# LEDs.net
KiCad netlist of a schematic drawn in Altium Designer
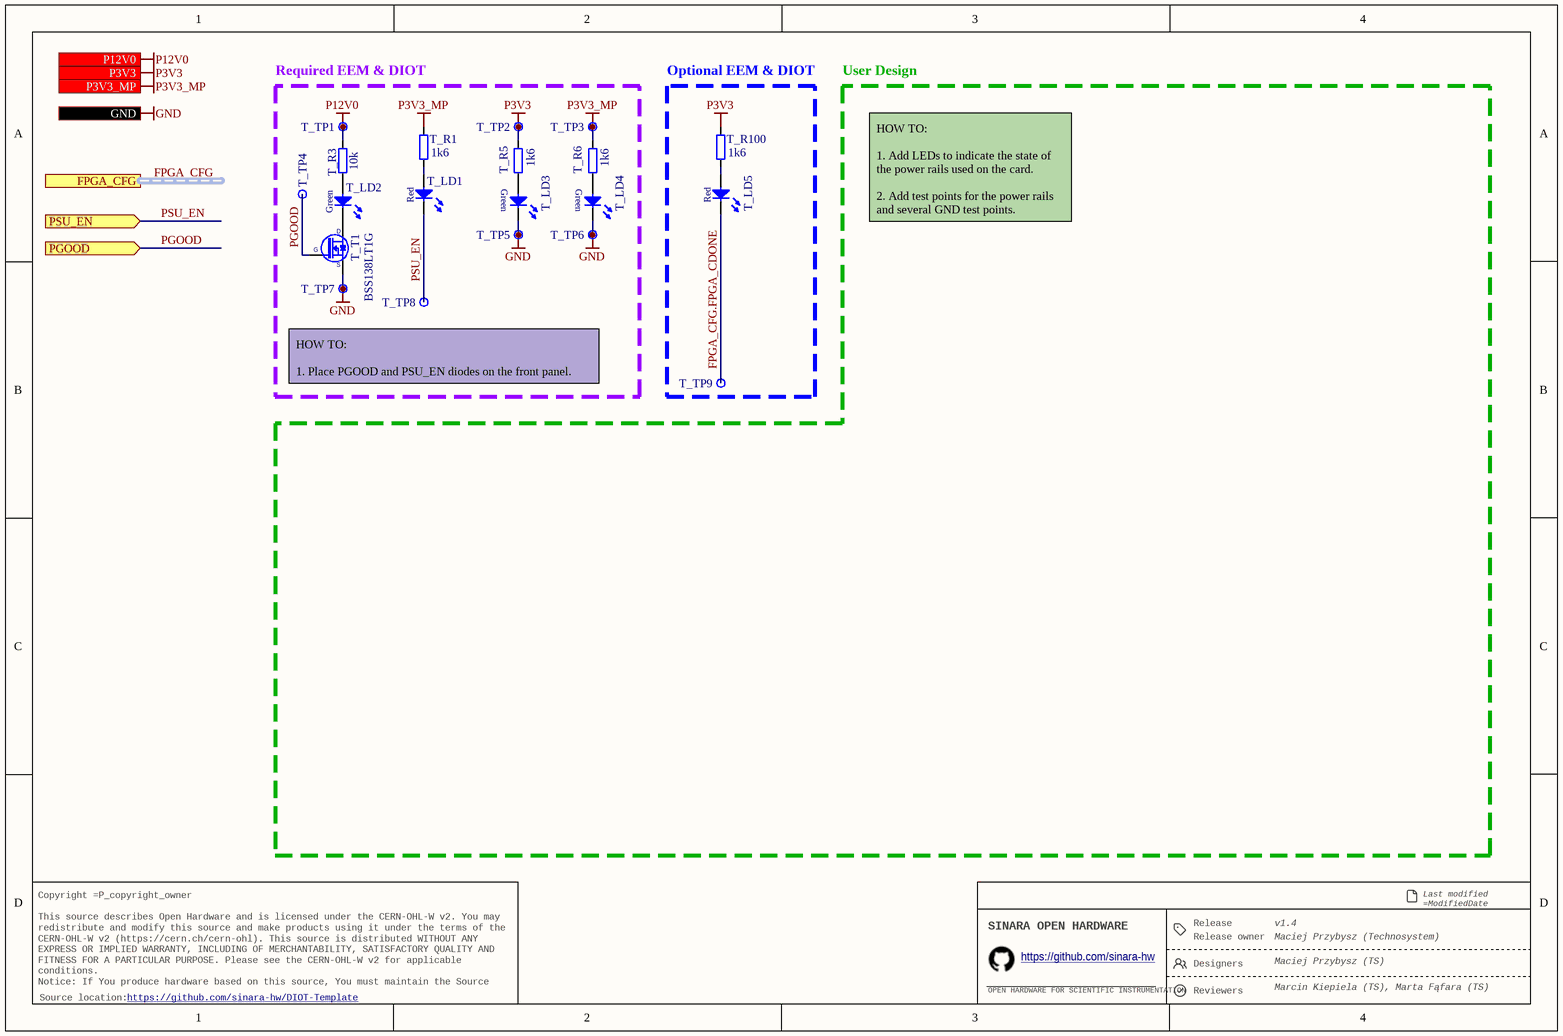
[diagram p0: LEDs.SchDoc]

(export (version "E")
  (design (tool "Eeschema 10.0.6"))
  (components
    (comp (ref "T_LD1")
      (value "Red")
      (footprint "LED_AVAGO_HSMC-C110")
      (description "LED Red 1C 2A")
      (fields
        (field (name "PART NUMBER") "LED_AVAGO_HSMC-C110")
        (field (name "MANUFACTURER") "AVAGO TECHNOLOGIES")
        (field (name "AUTHOR") "CERN DEM JMW")
      )
      (libsource (lib "ICs And Semiconductors") (part "LED Red 1C 2A"))
    )
    (comp (ref "T_LD2")
      (value "Green")
      (footprint "LED_AVAGO_HSME-C110")
      (description "LED Green 1C 2A")
      (fields
        (field (name "PART NUMBER") "LED_AVAGO_HSME-C110")
        (field (name "MANUFACTURER") "AVAGO TECHNOLOGIES")
        (field (name "AUTHOR") "CERN DEM JMW")
      )
      (libsource (lib "") (part "LED Green 1C 2A_1"))
    )
    (comp (ref "T_LD3")
      (value "Green")
      (footprint "LED_KINGBRIGHT_KPH-1608CGCK")
      (description "LED Green 1C 2A")
      (fields
        (field (name "PART NUMBER") "LED_KINGBRIGHT_KPH-1608CGCK")
        (field (name "MANUFACTURER") "KINGBRIGHT")
        (field (name "AUTHOR") "CERN DEM JLC")
      )
      (libsource (lib "ICs And Semiconductors") (part "LED Green 1C 2A"))
    )
    (comp (ref "T_LD4")
      (value "Green")
      (footprint "LED_KINGBRIGHT_KPH-1608CGCK")
      (description "LED Green 1C 2A")
      (fields
        (field (name "PART NUMBER") "LED_KINGBRIGHT_KPH-1608CGCK")
        (field (name "MANUFACTURER") "KINGBRIGHT")
        (field (name "AUTHOR") "CERN DEM JLC")
      )
      (libsource (lib "ICs And Semiconductors") (part "LED Green 1C 2A"))
    )
    (comp (ref "T_LD5")
      (value "Red")
      (footprint "LED_AVAGO_HSMC-C110")
      (description "LED Red 1C 2A")
      (fields
        (field (name "PART NUMBER") "LED_AVAGO_HSMC-C110")
        (field (name "MANUFACTURER") "AVAGO TECHNOLOGIES")
        (field (name "AUTHOR") "CERN DEM JMW")
      )
      (libsource (lib "ICs And Semiconductors") (part "LED Red 1C 2A"))
    )
    (comp (ref "T_R1")
      (value "1k6")
      (footprint "RESC1005X40N")
      (description "Resistor - 1%")
      (fields
        (field (name "PART NUMBER") "R0402_1K6_1%_0.0625W_100PPM")
        (field (name "POWER") "0.0625W")
        (field (name "AUTHOR") "CERN DEM JLC")
      )
      (libsource (lib "Resistors") (part "Resistor - 1%"))
    )
    (comp (ref "T_R3")
      (value "10k")
      (footprint "RESC1005X40N")
      (description "Resistor - 1%")
      (fields
        (field (name "PART NUMBER") "R0402_10K_1%_0.0625W_100PPM")
        (field (name "POWER") "0.0625W")
        (field (name "AUTHOR") "CERN DEM JLC")
      )
      (libsource (lib "Resistors") (part "Resistor - 1%"))
    )
    (comp (ref "T_R5")
      (value "1k6")
      (footprint "RESC1005X40N")
      (description "Resistor - 1%")
      (fields
        (field (name "PART NUMBER") "R0402_1K6_1%_0.0625W_100PPM")
        (field (name "POWER") "0.0625W")
        (field (name "AUTHOR") "CERN DEM JLC")
      )
      (libsource (lib "Resistors") (part "Resistor - 1%"))
    )
    (comp (ref "T_R6")
      (value "1k6")
      (footprint "RESC1005X40N")
      (description "Resistor - 1%")
      (fields
        (field (name "PART NUMBER") "R0402_1K6_1%_0.0625W_100PPM")
        (field (name "POWER") "0.0625W")
        (field (name "AUTHOR") "CERN DEM JLC")
      )
      (libsource (lib "Resistors") (part "Resistor - 1%"))
    )
    (comp (ref "T_R100")
      (value "1k6")
      (footprint "RESC1005X40N")
      (description "Resistor - 1%")
      (fields
        (field (name "PART NUMBER") "R0402_1K6_1%_0.0625W_100PPM")
        (field (name "POWER") "0.0625W")
        (field (name "AUTHOR") "CERN DEM JLC")
      )
      (libsource (lib "Resistors") (part "Resistor - 1%"))
    )
    (comp (ref "T_T1")
      (value "BSS138LT1G")
      (footprint "SOT95P240X110-3N")
      (description "N-CHANNEL MOSFET WITH DIODE")
      (fields
        (field (name "MANUFACTURER") "ON SEMICONDUCTOR")
        (field (name "MANUFACTURER PART NUMBER") "BSS138L")
        (field (name "AUTHOR") "CERN DEM JLC")
      )
      (libsource (lib "ICs And Semiconductors") (part "N-MOSFET-D 1G 2S 3D"))
    )
    (comp (ref "T_TP1")
      (value "Test Point")
      (footprint "TPS127")
      (fields (field (name "PART NUMBER") "SMD_PAD_1.27X1.27MM") (field (name "AUTHOR") "CERN DEM JLC"))
      (libsource (lib "Eletro-mechanical") (part "Test Point"))
    )
    (comp (ref "T_TP2")
      (value "Test Point")
      (footprint "TPS127")
      (fields (field (name "PART NUMBER") "SMD_PAD_1.27X1.27MM") (field (name "AUTHOR") "CERN DEM JLC"))
      (libsource (lib "Eletro-mechanical") (part "Test Point"))
    )
    (comp (ref "T_TP3")
      (value "Test Point")
      (footprint "TPS127")
      (fields (field (name "PART NUMBER") "SMD_PAD_1.27X1.27MM") (field (name "AUTHOR") "CERN DEM JLC"))
      (libsource (lib "Eletro-mechanical") (part "Test Point"))
    )
    (comp (ref "T_TP4")
      (value "Test Point")
      (footprint "TPS127")
      (fields (field (name "PART NUMBER") "SMD_PAD_1.27X1.27MM") (field (name "AUTHOR") "CERN DEM JLC"))
      (libsource (lib "Eletro-mechanical") (part "Test Point"))
    )
    (comp (ref "T_TP5")
      (value "Test Point")
      (footprint "TPS127")
      (fields (field (name "PART NUMBER") "SMD_PAD_1.27X1.27MM") (field (name "AUTHOR") "CERN DEM JLC"))
      (libsource (lib "Eletro-mechanical") (part "Test Point"))
    )
    (comp (ref "T_TP6")
      (value "Test Point")
      (footprint "TPS127")
      (fields (field (name "PART NUMBER") "SMD_PAD_1.27X1.27MM") (field (name "AUTHOR") "CERN DEM JLC"))
      (libsource (lib "Eletro-mechanical") (part "Test Point"))
    )
    (comp (ref "T_TP7")
      (value "Test Point")
      (footprint "TPS127")
      (fields (field (name "PART NUMBER") "SMD_PAD_1.27X1.27MM") (field (name "AUTHOR") "CERN DEM JLC"))
      (libsource (lib "Eletro-mechanical") (part "Test Point"))
    )
    (comp (ref "T_TP8")
      (value "Test Point")
      (footprint "TPS127")
      (fields (field (name "PART NUMBER") "SMD_PAD_1.27X1.27MM") (field (name "AUTHOR") "CERN DEM JLC"))
      (libsource (lib "Eletro-mechanical") (part "Test Point"))
    )
    (comp (ref "T_TP9")
      (value "Test Point")
      (footprint "TPS127")
      (fields (field (name "PART NUMBER") "SMD_PAD_1.27X1.27MM") (field (name "AUTHOR") "CERN DEM JLC"))
      (libsource (lib "Eletro-mechanical") (part "Test Point"))
    )
  )
  (nets
    (net (code "2") (name "/FPGA_CFG.FPGA_CDONE") (class "Default")
      (node (ref "T_LD5") (pin "1") (pinfunction "C_1") (pintype "passive"))
      (node (ref "T_TP9") (pin "1") (pinfunction "1_1") (pintype "bidirectional"))
    )
    (net (code "3") (name "/PGOOD") (class "Default")
      (node (ref "T_T1") (pin "1") (pinfunction "G_1") (pintype "passive"))
      (node (ref "T_TP4") (pin "1") (pinfunction "1_1") (pintype "bidirectional"))
    )
    (net (code "4") (name "/PSU_EN") (class "Default")
      (node (ref "T_LD1") (pin "1") (pinfunction "C_1") (pintype "passive"))
      (node (ref "T_TP8") (pin "1") (pinfunction "1_1") (pintype "bidirectional"))
    )
    (net (code "6") (name "GND") (class "Default")
      (node (ref "T_LD3") (pin "1") (pinfunction "C_1") (pintype "passive"))
      (node (ref "T_LD4") (pin "1") (pinfunction "C_1") (pintype "passive"))
      (node (ref "T_T1") (pin "2") (pinfunction "S_2") (pintype "passive"))
      (node (ref "T_TP5") (pin "1") (pinfunction "1_1") (pintype "bidirectional"))
      (node (ref "T_TP6") (pin "1") (pinfunction "1_1") (pintype "bidirectional"))
      (node (ref "T_TP7") (pin "1") (pinfunction "1_1") (pintype "bidirectional"))
    )
    (net (code "7") (name "Net-(T_LD1-A)") (class "Default")
      (node (ref "T_LD1") (pin "2") (pinfunction "A_2") (pintype "passive"))
      (node (ref "T_R1") (pin "1") (pinfunction "1_1") (pintype "passive"))
    )
    (net (code "8") (name "Net-(T_LD2-A)") (class "Default")
      (node (ref "T_LD2") (pin "2") (pinfunction "A_2") (pintype "passive"))
      (node (ref "T_R3") (pin "2") (pinfunction "2_2") (pintype "passive"))
    )
    (net (code "9") (name "Net-(T_LD2-C)") (class "Default")
      (node (ref "T_LD2") (pin "1") (pinfunction "C_1") (pintype "passive"))
      (node (ref "T_T1") (pin "3") (pinfunction "D_3") (pintype "passive"))
    )
    (net (code "10") (name "Net-(T_LD3-A)") (class "Default")
      (node (ref "T_LD3") (pin "2") (pinfunction "A_2") (pintype "passive"))
      (node (ref "T_R5") (pin "1") (pinfunction "1_1") (pintype "passive"))
    )
    (net (code "11") (name "Net-(T_LD4-A)") (class "Default")
      (node (ref "T_LD4") (pin "2") (pinfunction "A_2") (pintype "passive"))
      (node (ref "T_R6") (pin "1") (pinfunction "1_1") (pintype "passive"))
    )
    (net (code "12") (name "Net-(T_LD5-A)") (class "Default")
      (node (ref "T_LD5") (pin "2") (pinfunction "A_2") (pintype "passive"))
      (node (ref "T_R100") (pin "1") (pinfunction "1_1") (pintype "passive"))
    )
    (net (code "13") (name "P3V3") (class "Default")
      (node (ref "T_R100") (pin "2") (pinfunction "2_2") (pintype "passive"))
      (node (ref "T_R5") (pin "2") (pinfunction "2_2") (pintype "passive"))
      (node (ref "T_TP2") (pin "1") (pinfunction "1_1") (pintype "bidirectional"))
    )
    (net (code "14") (name "P3V3_MP") (class "Default")
      (node (ref "T_R1") (pin "2") (pinfunction "2_2") (pintype "passive"))
      (node (ref "T_R6") (pin "2") (pinfunction "2_2") (pintype "passive"))
      (node (ref "T_TP3") (pin "1") (pinfunction "1_1") (pintype "bidirectional"))
    )
    (net (code "15") (name "P12V0") (class "Default")
      (node (ref "T_R3") (pin "1") (pinfunction "1_1") (pintype "passive"))
      (node (ref "T_TP1") (pin "1") (pinfunction "1_1") (pintype "bidirectional"))
    )
  )
)
